# gateway_r0.net
KiCad netlist of a schematic drawn in EAGLE
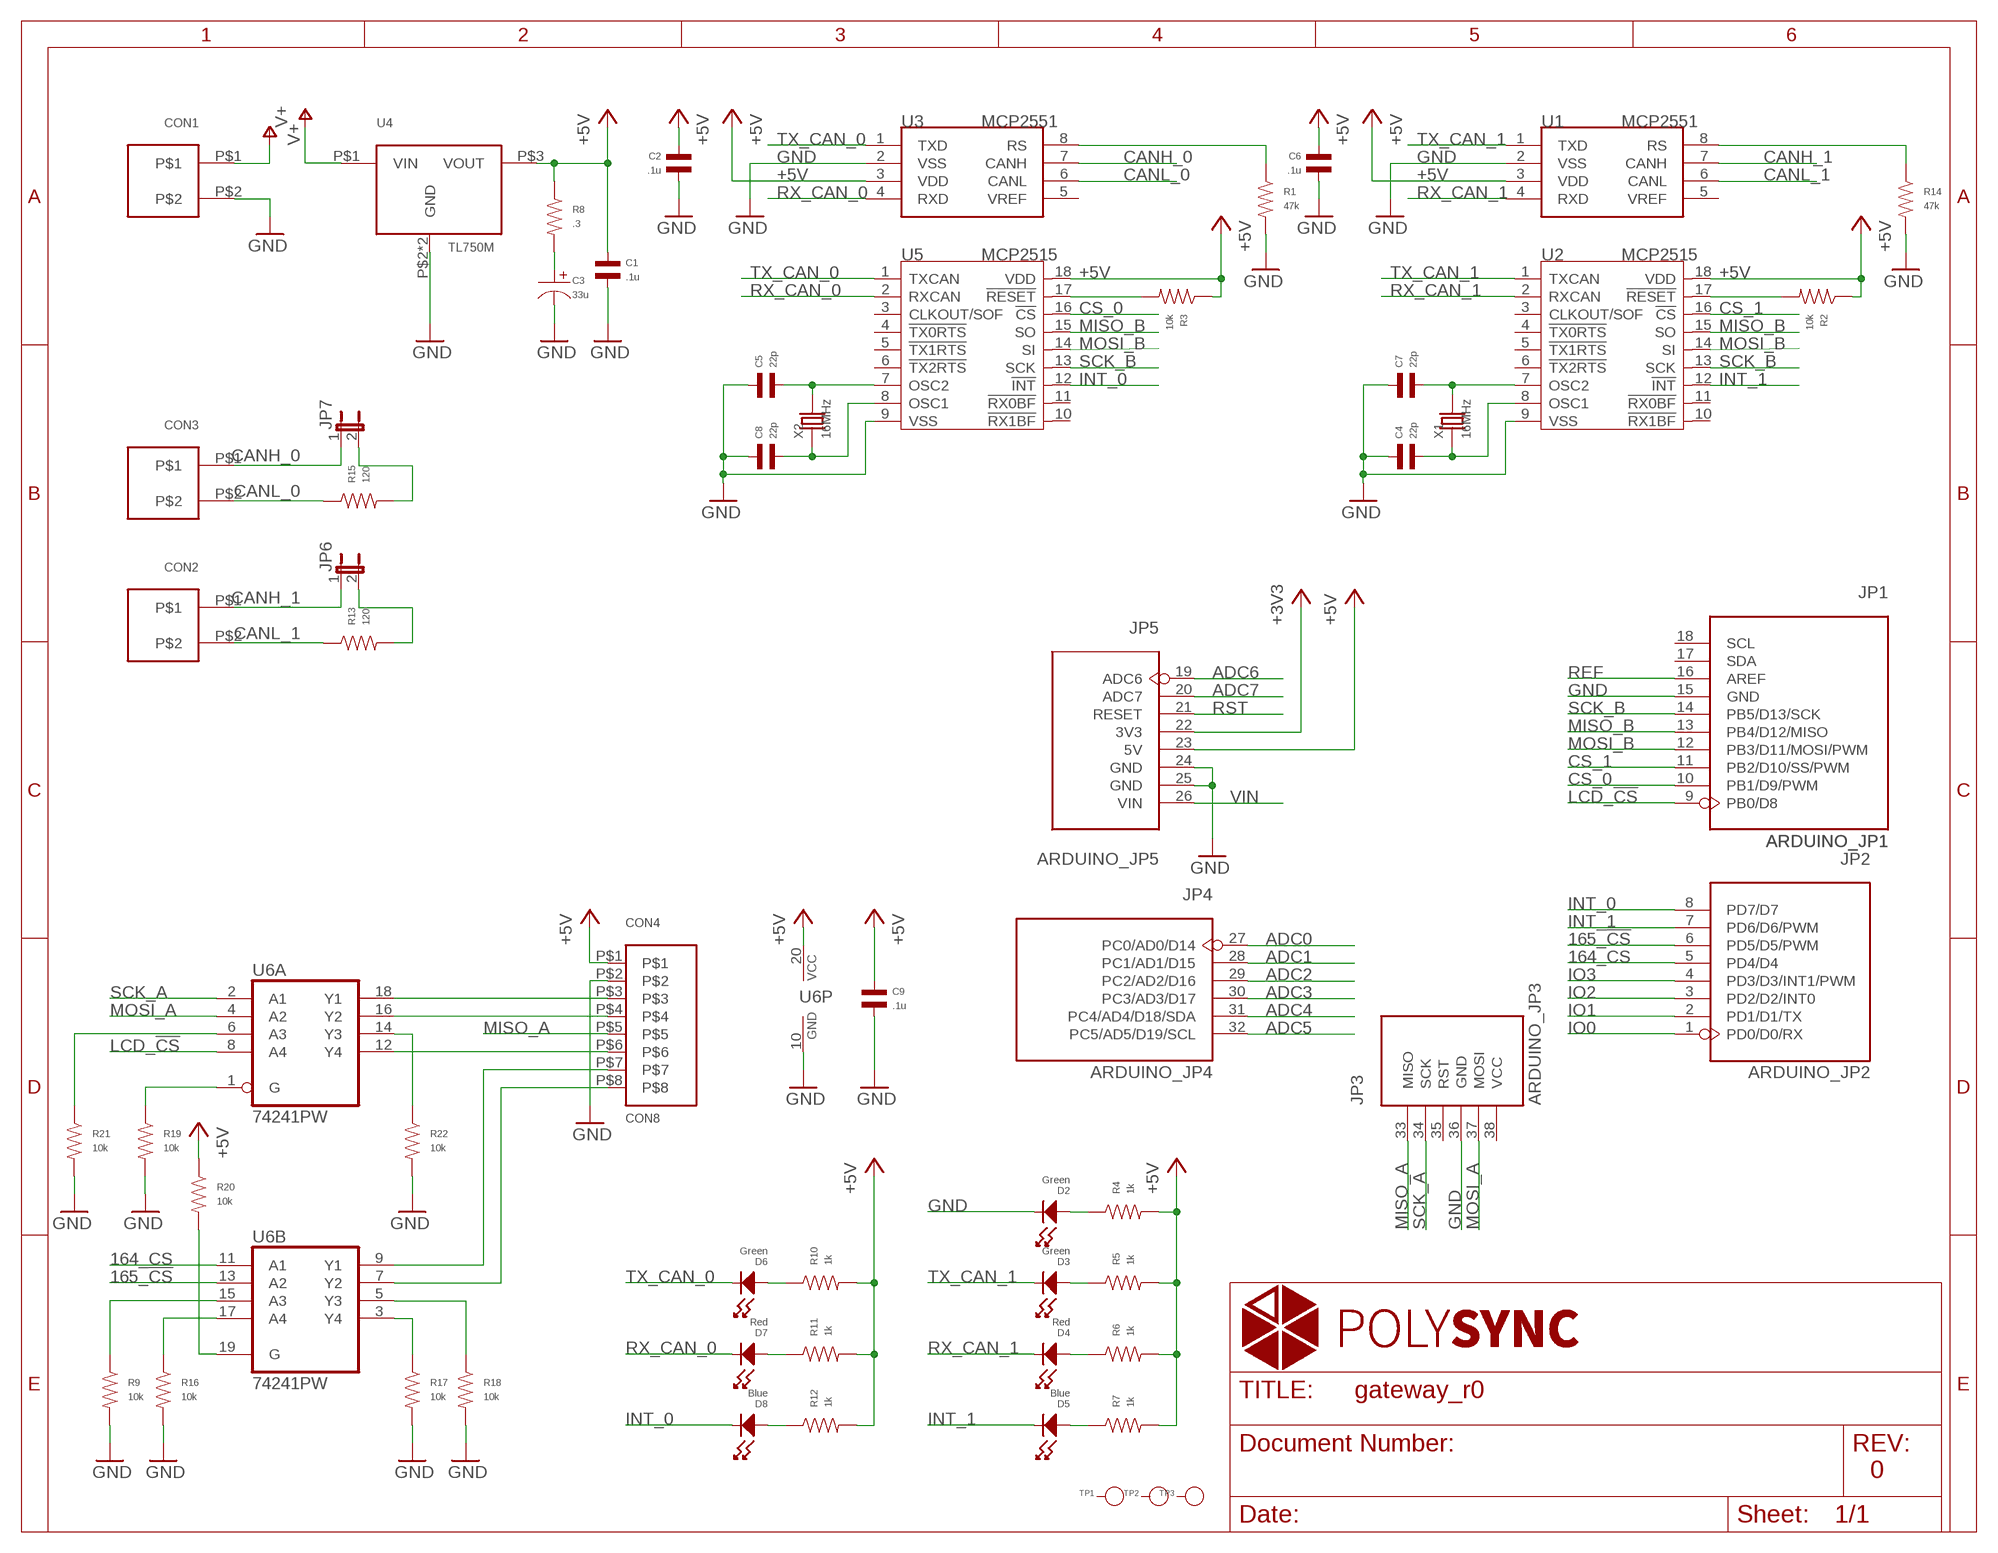
[diagram p0: schematic, sheet 1]

(export (version "E")
  (design (tool "Eeschema 10.0.6"))
  (components
    (comp (ref "C1")
      (value ".1u")
      (footprint "eagle-import:C0402")
      (libsource (lib "eagle-import") (part "CAPACITOR_NP_0402"))
    )
    (comp (ref "C2")
      (value ".1u")
      (footprint "eagle-import:C0402")
      (libsource (lib "eagle-import") (part "CAPACITOR_NP_0402"))
    )
    (comp (ref "C3")
      (value "33u")
      (footprint "eagle-import:CP1206")
      (libsource (lib "eagle-import") (part "CAPACITOR_P"))
    )
    (comp (ref "C4")
      (value "22p")
      (footprint "eagle-import:C0402")
      (libsource (lib "eagle-import") (part "CAPACITOR_NP_0402"))
    )
    (comp (ref "C5")
      (value "22p")
      (footprint "eagle-import:C0402")
      (libsource (lib "eagle-import") (part "CAPACITOR_NP_0402"))
    )
    (comp (ref "C6")
      (value ".1u")
      (footprint "eagle-import:C0402")
      (libsource (lib "eagle-import") (part "CAPACITOR_NP_0402"))
    )
    (comp (ref "C7")
      (value "22p")
      (footprint "eagle-import:C0402")
      (libsource (lib "eagle-import") (part "CAPACITOR_NP_0402"))
    )
    (comp (ref "C8")
      (value "22p")
      (footprint "eagle-import:C0402")
      (libsource (lib "eagle-import") (part "CAPACITOR_NP_0402"))
    )
    (comp (ref "C9")
      (value ".1u")
      (footprint "eagle-import:C0402")
      (libsource (lib "eagle-import") (part "CAPACITOR_NP_0402"))
    )
    (comp (ref "CON1")
      (value "CON23.5MM")
      (footprint "eagle-import:PHOENIX_2_45")
      (libsource (lib "eagle-import") (part "CON23.5MM"))
    )
    (comp (ref "CON2")
      (value "CON23.5MM")
      (footprint "eagle-import:PHOENIX_2_45")
      (libsource (lib "eagle-import") (part "CON23.5MM"))
    )
    (comp (ref "CON3")
      (value "CON23.5MM")
      (footprint "eagle-import:PHOENIX_2_45")
      (libsource (lib "eagle-import") (part "CON23.5MM"))
    )
    (comp (ref "CON4")
      (value "CON8")
      (footprint "eagle-import:PH-8-SM")
      (libsource (lib "eagle-import") (part "CON8"))
    )
    (comp (ref "D2")
      (value "Green")
      (footprint "eagle-import:LED0603")
      (fields (field (name "HOUSEPART") "NO"))
      (libsource (lib "eagle-import") (part "LED_SINGLE-0603"))
    )
    (comp (ref "D3")
      (value "Green")
      (footprint "eagle-import:LED0603")
      (fields (field (name "HOUSEPART") "NO"))
      (libsource (lib "eagle-import") (part "LED_SINGLE-0603"))
    )
    (comp (ref "D4")
      (value "Red")
      (footprint "eagle-import:LED0603")
      (fields (field (name "HOUSEPART") "NO"))
      (libsource (lib "eagle-import") (part "LED_SINGLE-0603"))
    )
    (comp (ref "D5")
      (value "Blue")
      (footprint "eagle-import:LED0603")
      (fields (field (name "HOUSEPART") "NO"))
      (libsource (lib "eagle-import") (part "LED_SINGLE-0603"))
    )
    (comp (ref "D6")
      (value "Green")
      (footprint "eagle-import:LED0603")
      (fields (field (name "HOUSEPART") "NO"))
      (libsource (lib "eagle-import") (part "LED_SINGLE-0603"))
    )
    (comp (ref "D7")
      (value "Red")
      (footprint "eagle-import:LED0603")
      (fields (field (name "HOUSEPART") "NO"))
      (libsource (lib "eagle-import") (part "LED_SINGLE-0603"))
    )
    (comp (ref "D8")
      (value "Blue")
      (footprint "eagle-import:LED0603")
      (fields (field (name "HOUSEPART") "NO"))
      (libsource (lib "eagle-import") (part "LED_SINGLE-0603"))
    )
    (comp (ref "JP1")
      (value "ARDUINO_JP1")
      (footprint "eagle-import:ARDUINO_JP1")
      (libsource (lib "eagle-import") (part "ARDUINO_JP1"))
    )
    (comp (ref "JP2")
      (value "ARDUINO_JP2")
      (footprint "eagle-import:ARDUINO_JP2")
      (libsource (lib "eagle-import") (part "ARDUINO_JP2"))
    )
    (comp (ref "JP3")
      (value "ARDUINO_JP3")
      (footprint "eagle-import:ARDUINO_JP3")
      (libsource (lib "eagle-import") (part "ARDUINO_JP3"))
    )
    (comp (ref "JP4")
      (value "ARDUINO_JP4")
      (footprint "eagle-import:ARDUINO_JP4")
      (libsource (lib "eagle-import") (part "ARDUINO_JP4"))
    )
    (comp (ref "JP5")
      (value "ARDUINO_JP5")
      (footprint "eagle-import:ARDUINO_JP5")
      (libsource (lib "eagle-import") (part "ARDUINO_JP5"))
    )
    (comp (ref "JP6")
      (value "JP1E")
      (footprint "eagle-import:JP1")
      (libsource (lib "eagle-import") (part "JP1E"))
    )
    (comp (ref "JP7")
      (value "JP1E")
      (footprint "eagle-import:JP1")
      (libsource (lib "eagle-import") (part "JP1E"))
    )
    (comp (ref "R1")
      (value "47k")
      (footprint "eagle-import:R0402")
      (libsource (lib "eagle-import") (part "RESISTOR_0402"))
    )
    (comp (ref "R2")
      (value "10k")
      (footprint "eagle-import:R0402")
      (libsource (lib "eagle-import") (part "RESISTOR_0402"))
    )
    (comp (ref "R3")
      (value "10k")
      (footprint "eagle-import:R0402")
      (libsource (lib "eagle-import") (part "RESISTOR_0402"))
    )
    (comp (ref "R4")
      (value "1k")
      (footprint "eagle-import:R0402")
      (libsource (lib "eagle-import") (part "RESISTOR_0402"))
    )
    (comp (ref "R5")
      (value "1k")
      (footprint "eagle-import:R0402")
      (libsource (lib "eagle-import") (part "RESISTOR_0402"))
    )
    (comp (ref "R6")
      (value "1k")
      (footprint "eagle-import:R0402")
      (libsource (lib "eagle-import") (part "RESISTOR_0402"))
    )
    (comp (ref "R7")
      (value "1k")
      (footprint "eagle-import:R0402")
      (libsource (lib "eagle-import") (part "RESISTOR_0402"))
    )
    (comp (ref "R8")
      (value ".3")
      (footprint "eagle-import:R0402")
      (libsource (lib "eagle-import") (part "RESISTOR_0402"))
    )
    (comp (ref "R9")
      (value "10k")
      (footprint "eagle-import:R0402")
      (libsource (lib "eagle-import") (part "RESISTOR_0402"))
    )
    (comp (ref "R10")
      (value "1k")
      (footprint "eagle-import:R0402")
      (libsource (lib "eagle-import") (part "RESISTOR_0402"))
    )
    (comp (ref "R11")
      (value "1k")
      (footprint "eagle-import:R0402")
      (libsource (lib "eagle-import") (part "RESISTOR_0402"))
    )
    (comp (ref "R12")
      (value "1k")
      (footprint "eagle-import:R0402")
      (libsource (lib "eagle-import") (part "RESISTOR_0402"))
    )
    (comp (ref "R13")
      (value "120")
      (footprint "eagle-import:R0402")
      (libsource (lib "eagle-import") (part "RESISTOR_0402"))
    )
    (comp (ref "R14")
      (value "47k")
      (footprint "eagle-import:R0402")
      (libsource (lib "eagle-import") (part "RESISTOR_0402"))
    )
    (comp (ref "R15")
      (value "120")
      (footprint "eagle-import:R0402")
      (libsource (lib "eagle-import") (part "RESISTOR_0402"))
    )
    (comp (ref "R16")
      (value "10k")
      (footprint "eagle-import:R0402")
      (libsource (lib "eagle-import") (part "RESISTOR_0402"))
    )
    (comp (ref "R17")
      (value "10k")
      (footprint "eagle-import:R0402")
      (libsource (lib "eagle-import") (part "RESISTOR_0402"))
    )
    (comp (ref "R18")
      (value "10k")
      (footprint "eagle-import:R0402")
      (libsource (lib "eagle-import") (part "RESISTOR_0402"))
    )
    (comp (ref "R19")
      (value "10k")
      (footprint "eagle-import:R0402")
      (libsource (lib "eagle-import") (part "RESISTOR_0402"))
    )
    (comp (ref "R20")
      (value "10k")
      (footprint "eagle-import:R0402")
      (libsource (lib "eagle-import") (part "RESISTOR_0402"))
    )
    (comp (ref "R21")
      (value "10k")
      (footprint "eagle-import:R0402")
      (libsource (lib "eagle-import") (part "RESISTOR_0402"))
    )
    (comp (ref "R22")
      (value "10k")
      (footprint "eagle-import:R0402")
      (libsource (lib "eagle-import") (part "RESISTOR_0402"))
    )
    (comp (ref "TP1")
      (value "PAD-TEST-POINT'4545'")
      (footprint "eagle-import:TP_4545")
      (fields (field (name "PARTNO") "DNP"))
      (libsource (lib "eagle-import") (part "PAD-TEST-POINT'4545'"))
    )
    (comp (ref "TP2")
      (value "PAD-TEST-POINT'4545'")
      (footprint "eagle-import:TP_4545")
      (fields (field (name "PARTNO") "DNP"))
      (libsource (lib "eagle-import") (part "PAD-TEST-POINT'4545'"))
    )
    (comp (ref "TP3")
      (value "PAD-TEST-POINT'4545'")
      (footprint "eagle-import:TP_4545")
      (fields (field (name "PARTNO") "DNP"))
      (libsource (lib "eagle-import") (part "PAD-TEST-POINT'4545'"))
    )
    (comp (ref "U1")
      (value "MCP2551")
      (footprint "eagle-import:SOIC8-6.0")
      (libsource (lib "eagle-import") (part "MCP2551-SOIC8"))
    )
    (comp (ref "U2")
      (value "MCP2515")
      (footprint "eagle-import:SOIC18")
      (libsource (lib "eagle-import") (part "MCP2515-SOIC18"))
    )
    (comp (ref "U3")
      (value "MCP2551")
      (footprint "eagle-import:SOIC8-6.0")
      (libsource (lib "eagle-import") (part "MCP2551-SOIC8"))
    )
    (comp (ref "U4")
      (value "TL750M")
      (footprint "eagle-import:TO-263")
      (libsource (lib "eagle-import") (part "TL750M"))
    )
    (comp (ref "U5")
      (value "MCP2515")
      (footprint "eagle-import:SOIC18")
      (libsource (lib "eagle-import") (part "MCP2515-SOIC18"))
    )
    (comp (ref "U6")
      (value "74241PW")
      (footprint "eagle-import:PW_R-PDSO-G20")
      (libsource (lib "eagle-import") (part "74241PW"))
    )
    (comp (ref "X1")
      (value "16MHz")
      (footprint "eagle-import:HC49UP")
      (libsource (lib "eagle-import") (part "CRYSTAL-HC49UP"))
    )
    (comp (ref "X2")
      (value "16MHz")
      (footprint "eagle-import:HC49UP")
      (libsource (lib "eagle-import") (part "CRYSTAL-HC49UP"))
    )
  )
  (nets
    (net (code "1") (name "+3V3") (class "Default")
      (node (ref "JP5") (pin "22") (pinfunction "3V3_22") (pintype "bidirectional"))
    )
    (net (code "2") (name "+5V") (class "Default")
      (node (ref "C1") (pin "P$1") (pinfunction "P$1_P$1") (pintype "passive"))
      (node (ref "C2") (pin "P$1") (pinfunction "P$1_P$1") (pintype "passive"))
      (node (ref "C6") (pin "P$1") (pinfunction "P$1_P$1") (pintype "passive"))
      (node (ref "C9") (pin "P$1") (pinfunction "P$1_P$1") (pintype "passive"))
      (node (ref "CON4") (pin "P$1") (pinfunction "P$1_P$1") (pintype "bidirectional"))
      (node (ref "JP5") (pin "23") (pinfunction "5V_23") (pintype "bidirectional"))
      (node (ref "R10") (pin "P$2") (pinfunction "P$2_P$2") (pintype "passive"))
      (node (ref "R11") (pin "P$2") (pinfunction "P$2_P$2") (pintype "passive"))
      (node (ref "R12") (pin "P$2") (pinfunction "P$2_P$2") (pintype "passive"))
      (node (ref "R2") (pin "P$1") (pinfunction "P$1_P$1") (pintype "passive"))
      (node (ref "R20") (pin "P$1") (pinfunction "P$1_P$1") (pintype "passive"))
      (node (ref "R3") (pin "P$1") (pinfunction "P$1_P$1") (pintype "passive"))
      (node (ref "R4") (pin "P$2") (pinfunction "P$2_P$2") (pintype "passive"))
      (node (ref "R5") (pin "P$2") (pinfunction "P$2_P$2") (pintype "passive"))
      (node (ref "R6") (pin "P$2") (pinfunction "P$2_P$2") (pintype "passive"))
      (node (ref "R7") (pin "P$2") (pinfunction "P$2_P$2") (pintype "passive"))
      (node (ref "R8") (pin "P$1") (pinfunction "P$1_P$1") (pintype "passive"))
      (node (ref "U1") (pin "3") (pinfunction "VDD_3") (pintype "bidirectional"))
      (node (ref "U2") (pin "18") (pinfunction "VDD_18") (pintype "power_in"))
      (node (ref "U3") (pin "3") (pinfunction "VDD_3") (pintype "bidirectional"))
      (node (ref "U4") (pin "P$3") (pinfunction "VOUT_P$3") (pintype "bidirectional"))
      (node (ref "U5") (pin "18") (pinfunction "VDD_18") (pintype "power_in"))
      (node (ref "U6") (pin "20") (pinfunction "VCC_20") (pintype "power_in"))
    )
    (net (code "3") (name "/164_CS") (class "Default")
      (node (ref "JP2") (pin "5") (pinfunction "PD4/D4_5") (pintype "bidirectional"))
      (node (ref "U6") (pin "11") (pinfunction "A1_11") (pintype "input"))
    )
    (net (code "4") (name "/165_~{CS}") (class "Default")
      (node (ref "JP2") (pin "6") (pinfunction "PD5/D5/PWM_6") (pintype "bidirectional"))
      (node (ref "U6") (pin "13") (pinfunction "A2_13") (pintype "input"))
    )
    (net (code "5") (name "/ADC0") (class "Default")
      (node (ref "JP4") (pin "27") (pinfunction "PC0/AD0/D14_27") (pintype "bidirectional"))
    )
    (net (code "6") (name "/ADC1") (class "Default")
      (node (ref "JP4") (pin "28") (pinfunction "PC1/AD1/D15_28") (pintype "bidirectional"))
    )
    (net (code "7") (name "/ADC2") (class "Default")
      (node (ref "JP4") (pin "29") (pinfunction "PC2/AD2/D16_29") (pintype "bidirectional"))
    )
    (net (code "8") (name "/ADC3") (class "Default")
      (node (ref "JP4") (pin "30") (pinfunction "PC3/AD3/D17_30") (pintype "bidirectional"))
    )
    (net (code "9") (name "/ADC4") (class "Default")
      (node (ref "JP4") (pin "31") (pinfunction "PC4/AD4/D18/SDA_31") (pintype "bidirectional"))
    )
    (net (code "10") (name "/ADC5") (class "Default")
      (node (ref "JP4") (pin "32") (pinfunction "PC5/AD5/D19/SCL_32") (pintype "bidirectional"))
    )
    (net (code "11") (name "/ADC6") (class "Default")
      (node (ref "JP5") (pin "19") (pinfunction "ADC6_19") (pintype "bidirectional"))
    )
    (net (code "12") (name "/ADC7") (class "Default")
      (node (ref "JP5") (pin "20") (pinfunction "ADC7_20") (pintype "bidirectional"))
    )
    (net (code "13") (name "/CANH_0") (class "Default")
      (node (ref "CON3") (pin "P$1") (pinfunction "P$1_P$1") (pintype "bidirectional"))
      (node (ref "JP7") (pin "1") (pinfunction "1_1") (pintype "passive"))
      (node (ref "U3") (pin "7") (pinfunction "CANH_7") (pintype "bidirectional"))
    )
    (net (code "14") (name "/CANH_1") (class "Default")
      (node (ref "CON2") (pin "P$1") (pinfunction "P$1_P$1") (pintype "bidirectional"))
      (node (ref "JP6") (pin "1") (pinfunction "1_1") (pintype "passive"))
      (node (ref "U1") (pin "7") (pinfunction "CANH_7") (pintype "bidirectional"))
    )
    (net (code "15") (name "/CANL_0") (class "Default")
      (node (ref "CON3") (pin "P$2") (pinfunction "P$2_P$2") (pintype "bidirectional"))
      (node (ref "R15") (pin "P$1") (pinfunction "P$1_P$1") (pintype "passive"))
      (node (ref "U3") (pin "6") (pinfunction "CANL_6") (pintype "bidirectional"))
    )
    (net (code "16") (name "/CANL_1") (class "Default")
      (node (ref "CON2") (pin "P$2") (pinfunction "P$2_P$2") (pintype "bidirectional"))
      (node (ref "R13") (pin "P$1") (pinfunction "P$1_P$1") (pintype "passive"))
      (node (ref "U1") (pin "6") (pinfunction "CANL_6") (pintype "bidirectional"))
    )
    (net (code "17") (name "/CS_0") (class "Default")
      (node (ref "JP1") (pin "10") (pinfunction "PB1/D9/PWM_10") (pintype "bidirectional"))
      (node (ref "U5") (pin "16") (pinfunction "~{CS}_16") (pintype "input"))
    )
    (net (code "18") (name "/CS_1") (class "Default")
      (node (ref "JP1") (pin "11") (pinfunction "PB2/D10/SS/PWM_11") (pintype "bidirectional"))
      (node (ref "U2") (pin "16") (pinfunction "~{CS}_16") (pintype "input"))
    )
    (net (code "19") (name "/INT_0") (class "Default")
      (node (ref "D8") (pin "CATHODE") (pinfunction "CATHODE_CATHODE") (pintype "power_in"))
      (node (ref "JP2") (pin "8") (pinfunction "PD7/D7_8") (pintype "bidirectional"))
      (node (ref "U5") (pin "12") (pinfunction "~{INT}_12") (pintype "output"))
    )
    (net (code "20") (name "/INT_1") (class "Default")
      (node (ref "D5") (pin "CATHODE") (pinfunction "CATHODE_CATHODE") (pintype "power_in"))
      (node (ref "JP2") (pin "7") (pinfunction "PD6/D6/PWM_7") (pintype "bidirectional"))
      (node (ref "U2") (pin "12") (pinfunction "~{INT}_12") (pintype "output"))
    )
    (net (code "21") (name "/IO0") (class "Default")
      (node (ref "JP2") (pin "1") (pinfunction "PD0/D0/RX_1") (pintype "bidirectional"))
    )
    (net (code "22") (name "/IO1") (class "Default")
      (node (ref "JP2") (pin "2") (pinfunction "PD1/D1/TX_2") (pintype "bidirectional"))
    )
    (net (code "23") (name "/IO2") (class "Default")
      (node (ref "JP2") (pin "3") (pinfunction "PD2/D2/INT0_3") (pintype "bidirectional"))
    )
    (net (code "24") (name "/IO3") (class "Default")
      (node (ref "JP2") (pin "4") (pinfunction "PD3/D3/INT1/PWM_4") (pintype "bidirectional"))
    )
    (net (code "25") (name "/LCD_~{CS}") (class "Default")
      (node (ref "JP1") (pin "9") (pinfunction "PB0/D8_9") (pintype "bidirectional"))
      (node (ref "U6") (pin "8") (pinfunction "A4_8") (pintype "input"))
    )
    (net (code "26") (name "/MISO_A") (class "Default")
      (node (ref "CON4") (pin "P$5") (pinfunction "P$5_P$5") (pintype "bidirectional"))
      (node (ref "JP3") (pin "33") (pinfunction "MISO_33") (pintype "bidirectional"))
    )
    (net (code "27") (name "/MISO_B") (class "Default")
      (node (ref "JP1") (pin "13") (pinfunction "PB4/D12/MISO_13") (pintype "bidirectional"))
      (node (ref "U2") (pin "15") (pinfunction "SO_15") (pintype "output"))
      (node (ref "U5") (pin "15") (pinfunction "SO_15") (pintype "output"))
    )
    (net (code "28") (name "/MOSI_A") (class "Default")
      (node (ref "JP3") (pin "37") (pinfunction "MOSI_37") (pintype "bidirectional"))
      (node (ref "U6") (pin "4") (pinfunction "A2_4") (pintype "input"))
    )
    (net (code "29") (name "/MOSI_B") (class "Default")
      (node (ref "JP1") (pin "12") (pinfunction "PB3/D11/MOSI/PWM_12") (pintype "bidirectional"))
      (node (ref "U2") (pin "14") (pinfunction "SI_14") (pintype "input"))
      (node (ref "U5") (pin "14") (pinfunction "SI_14") (pintype "input"))
    )
    (net (code "30") (name "/REF") (class "Default")
      (node (ref "JP1") (pin "16") (pinfunction "AREF_16") (pintype "bidirectional"))
    )
    (net (code "31") (name "/RST") (class "Default")
      (node (ref "JP5") (pin "21") (pinfunction "RESET_21") (pintype "bidirectional"))
    )
    (net (code "32") (name "/RX_CAN_0") (class "Default")
      (node (ref "D7") (pin "CATHODE") (pinfunction "CATHODE_CATHODE") (pintype "power_in"))
      (node (ref "U3") (pin "4") (pinfunction "RXD_4") (pintype "bidirectional"))
      (node (ref "U5") (pin "2") (pinfunction "RXCAN_2") (pintype "input"))
    )
    (net (code "33") (name "/RX_CAN_1") (class "Default")
      (node (ref "D4") (pin "CATHODE") (pinfunction "CATHODE_CATHODE") (pintype "power_in"))
      (node (ref "U1") (pin "4") (pinfunction "RXD_4") (pintype "bidirectional"))
      (node (ref "U2") (pin "2") (pinfunction "RXCAN_2") (pintype "input"))
    )
    (net (code "34") (name "/SCK_A") (class "Default")
      (node (ref "JP3") (pin "34") (pinfunction "SCK_34") (pintype "bidirectional"))
      (node (ref "U6") (pin "2") (pinfunction "A1_2") (pintype "input"))
    )
    (net (code "35") (name "/SCK_B") (class "Default")
      (node (ref "JP1") (pin "14") (pinfunction "PB5/D13/SCK_14") (pintype "bidirectional"))
      (node (ref "U2") (pin "13") (pinfunction "SCK_13") (pintype "input"))
      (node (ref "U5") (pin "13") (pinfunction "SCK_13") (pintype "input"))
    )
    (net (code "36") (name "/TX_CAN_0") (class "Default")
      (node (ref "D6") (pin "CATHODE") (pinfunction "CATHODE_CATHODE") (pintype "power_in"))
      (node (ref "U3") (pin "1") (pinfunction "TXD_1") (pintype "bidirectional"))
      (node (ref "U5") (pin "1") (pinfunction "TXCAN_1") (pintype "output"))
    )
    (net (code "37") (name "/TX_CAN_1") (class "Default")
      (node (ref "D3") (pin "CATHODE") (pinfunction "CATHODE_CATHODE") (pintype "power_in"))
      (node (ref "U1") (pin "1") (pinfunction "TXD_1") (pintype "bidirectional"))
      (node (ref "U2") (pin "1") (pinfunction "TXCAN_1") (pintype "output"))
    )
    (net (code "38") (name "/VIN") (class "Default")
      (node (ref "JP5") (pin "26") (pinfunction "VIN_26") (pintype "bidirectional"))
    )
    (net (code "39") (name "GND") (class "Default")
      (node (ref "C1") (pin "P$2") (pinfunction "P$2_P$2") (pintype "passive"))
      (node (ref "C2") (pin "P$2") (pinfunction "P$2_P$2") (pintype "passive"))
      (node (ref "C3") (pin "P$2") (pinfunction "P$2_P$2") (pintype "passive"))
      (node (ref "C4") (pin "P$1") (pinfunction "P$1_P$1") (pintype "passive"))
      (node (ref "C5") (pin "P$1") (pinfunction "P$1_P$1") (pintype "passive"))
      (node (ref "C6") (pin "P$2") (pinfunction "P$2_P$2") (pintype "passive"))
      (node (ref "C7") (pin "P$1") (pinfunction "P$1_P$1") (pintype "passive"))
      (node (ref "C8") (pin "P$1") (pinfunction "P$1_P$1") (pintype "passive"))
      (node (ref "C9") (pin "P$2") (pinfunction "P$2_P$2") (pintype "passive"))
      (node (ref "CON1") (pin "P$2") (pinfunction "P$2_P$2") (pintype "bidirectional"))
      (node (ref "CON4") (pin "P$2") (pinfunction "P$2_P$2") (pintype "bidirectional"))
      (node (ref "D2") (pin "CATHODE") (pinfunction "CATHODE_CATHODE") (pintype "power_in"))
      (node (ref "JP1") (pin "15") (pinfunction "GND_15") (pintype "bidirectional"))
      (node (ref "JP3") (pin "36") (pinfunction "GND_36") (pintype "bidirectional"))
      (node (ref "JP5") (pin "24") (pinfunction "GND_24") (pintype "bidirectional"))
      (node (ref "JP5") (pin "25") (pinfunction "GND_25") (pintype "bidirectional"))
      (node (ref "R1") (pin "P$2") (pinfunction "P$2_P$2") (pintype "passive"))
      (node (ref "R14") (pin "P$2") (pinfunction "P$2_P$2") (pintype "passive"))
      (node (ref "R16") (pin "P$2") (pinfunction "P$2_P$2") (pintype "passive"))
      (node (ref "R17") (pin "P$2") (pinfunction "P$2_P$2") (pintype "passive"))
      (node (ref "R18") (pin "P$2") (pinfunction "P$2_P$2") (pintype "passive"))
      (node (ref "R19") (pin "P$2") (pinfunction "P$2_P$2") (pintype "passive"))
      (node (ref "R21") (pin "P$2") (pinfunction "P$2_P$2") (pintype "passive"))
      (node (ref "R22") (pin "P$2") (pinfunction "P$2_P$2") (pintype "passive"))
      (node (ref "R9") (pin "P$2") (pinfunction "P$2_P$2") (pintype "passive"))
      (node (ref "U1") (pin "2") (pinfunction "VSS_2") (pintype "bidirectional"))
      (node (ref "U2") (pin "9") (pinfunction "VSS_9") (pintype "power_in"))
      (node (ref "U3") (pin "2") (pinfunction "VSS_2") (pintype "bidirectional"))
      (node (ref "U4") (pin "P$2") (pinfunction "GND_P$2") (pintype "bidirectional"))
      (node (ref "U4") (pin "P$4") (pinfunction "GND_P$4") (pintype "bidirectional"))
      (node (ref "U5") (pin "9") (pinfunction "VSS_9") (pintype "power_in"))
      (node (ref "U6") (pin "10") (pinfunction "GND_10") (pintype "power_in"))
    )
    (net (code "40") (name "Net-(C3-PadP$1)") (class "Default")
      (node (ref "C3") (pin "P$1") (pinfunction "P$1_P$1") (pintype "passive"))
      (node (ref "R8") (pin "P$2") (pinfunction "P$2_P$2") (pintype "passive"))
    )
    (net (code "41") (name "Net-(D2-PadANODE)") (class "Default")
      (node (ref "D2") (pin "ANODE") (pinfunction "ANODE_ANODE") (pintype "power_in"))
      (node (ref "R4") (pin "P$1") (pinfunction "P$1_P$1") (pintype "passive"))
    )
    (net (code "42") (name "Net-(D3-PadANODE)") (class "Default")
      (node (ref "D3") (pin "ANODE") (pinfunction "ANODE_ANODE") (pintype "power_in"))
      (node (ref "R5") (pin "P$1") (pinfunction "P$1_P$1") (pintype "passive"))
    )
    (net (code "43") (name "Net-(D4-PadANODE)") (class "Default")
      (node (ref "D4") (pin "ANODE") (pinfunction "ANODE_ANODE") (pintype "power_in"))
      (node (ref "R6") (pin "P$1") (pinfunction "P$1_P$1") (pintype "passive"))
    )
    (net (code "44") (name "Net-(D5-PadANODE)") (class "Default")
      (node (ref "D5") (pin "ANODE") (pinfunction "ANODE_ANODE") (pintype "power_in"))
      (node (ref "R7") (pin "P$1") (pinfunction "P$1_P$1") (pintype "passive"))
    )
    (net (code "45") (name "Net-(D6-PadANODE)") (class "Default")
      (node (ref "D6") (pin "ANODE") (pinfunction "ANODE_ANODE") (pintype "power_in"))
      (node (ref "R10") (pin "P$1") (pinfunction "P$1_P$1") (pintype "passive"))
    )
    (net (code "46") (name "Net-(D7-PadANODE)") (class "Default")
      (node (ref "D7") (pin "ANODE") (pinfunction "ANODE_ANODE") (pintype "power_in"))
      (node (ref "R11") (pin "P$1") (pinfunction "P$1_P$1") (pintype "passive"))
    )
    (net (code "47") (name "Net-(D8-PadANODE)") (class "Default")
      (node (ref "D8") (pin "ANODE") (pinfunction "ANODE_ANODE") (pintype "power_in"))
      (node (ref "R12") (pin "P$1") (pinfunction "P$1_P$1") (pintype "passive"))
    )
    (net (code "48") (name "Net-(JP6-Pad2)") (class "Default")
      (node (ref "JP6") (pin "2") (pinfunction "2_2") (pintype "passive"))
      (node (ref "R13") (pin "P$2") (pinfunction "P$2_P$2") (pintype "passive"))
    )
    (net (code "49") (name "Net-(JP7-Pad2)") (class "Default")
      (node (ref "JP7") (pin "2") (pinfunction "2_2") (pintype "passive"))
      (node (ref "R15") (pin "P$2") (pinfunction "P$2_P$2") (pintype "passive"))
    )
    (net (code "50") (name "Net-(U1-RS)") (class "Default")
      (node (ref "R14") (pin "P$1") (pinfunction "P$1_P$1") (pintype "passive"))
      (node (ref "U1") (pin "8") (pinfunction "RS_8") (pintype "bidirectional"))
    )
    (net (code "51") (name "Net-(U2-OSC1)") (class "Default")
      (node (ref "C4") (pin "P$2") (pinfunction "P$2_P$2") (pintype "passive"))
      (node (ref "U2") (pin "8") (pinfunction "OSC1_8") (pintype "input"))
      (node (ref "X1") (pin "1") (pinfunction "1_1") (pintype "passive"))
    )
    (net (code "52") (name "Net-(U2-OSC2)") (class "Default")
      (node (ref "C7") (pin "P$2") (pinfunction "P$2_P$2") (pintype "passive"))
      (node (ref "U2") (pin "7") (pinfunction "OSC2_7") (pintype "output"))
      (node (ref "X1") (pin "2") (pinfunction "2_2") (pintype "passive"))
    )
    (net (code "53") (name "Net-(U2-~{RESET})") (class "Default")
      (node (ref "R2") (pin "P$2") (pinfunction "P$2_P$2") (pintype "passive"))
      (node (ref "U2") (pin "17") (pinfunction "~{RESET}_17") (pintype "input"))
    )
    (net (code "54") (name "Net-(U3-RS)") (class "Default")
      (node (ref "R1") (pin "P$1") (pinfunction "P$1_P$1") (pintype "passive"))
      (node (ref "U3") (pin "8") (pinfunction "RS_8") (pintype "bidirectional"))
    )
    (net (code "55") (name "Net-(U5-OSC1)") (class "Default")
      (node (ref "C8") (pin "P$2") (pinfunction "P$2_P$2") (pintype "passive"))
      (node (ref "U5") (pin "8") (pinfunction "OSC1_8") (pintype "input"))
      (node (ref "X2") (pin "1") (pinfunction "1_1") (pintype "passive"))
    )
    (net (code "56") (name "Net-(U5-OSC2)") (class "Default")
      (node (ref "C5") (pin "P$2") (pinfunction "P$2_P$2") (pintype "passive"))
      (node (ref "U5") (pin "7") (pinfunction "OSC2_7") (pintype "output"))
      (node (ref "X2") (pin "2") (pinfunction "2_2") (pintype "passive"))
    )
    (net (code "57") (name "Net-(U5-~{RESET})") (class "Default")
      (node (ref "R3") (pin "P$2") (pinfunction "P$2_P$2") (pintype "passive"))
      (node (ref "U5") (pin "17") (pinfunction "~{RESET}_17") (pintype "input"))
    )
    (net (code "58") (name "Net-(U6A-A3)") (class "Default")
      (node (ref "R21") (pin "P$1") (pinfunction "P$1_P$1") (pintype "passive"))
      (node (ref "U6") (pin "6") (pinfunction "A3_6") (pintype "input"))
    )
    (net (code "59") (name "Net-(U6A-G)") (class "Default")
      (node (ref "R19") (pin "P$1") (pinfunction "P$1_P$1") (pintype "passive"))
      (node (ref "U6") (pin "1") (pinfunction "G_1") (pintype "input"))
    )
    (net (code "60") (name "Net-(U6A-Y1)") (class "Default")
      (node (ref "CON4") (pin "P$3") (pinfunction "P$3_P$3") (pintype "bidirectional"))
      (node (ref "U6") (pin "18") (pinfunction "Y1_18") (pintype "tri_state"))
    )
    (net (code "61") (name "Net-(U6A-Y2)") (class "Default")
      (node (ref "CON4") (pin "P$4") (pinfunction "P$4_P$4") (pintype "bidirectional"))
      (node (ref "U6") (pin "16") (pinfunction "Y2_16") (pintype "tri_state"))
    )
    (net (code "62") (name "Net-(U6A-Y3)") (class "Default")
      (node (ref "R22") (pin "P$1") (pinfunction "P$1_P$1") (pintype "passive"))
      (node (ref "U6") (pin "14") (pinfunction "Y3_14") (pintype "tri_state"))
    )
    (net (code "63") (name "Net-(U6A-Y4)") (class "Default")
      (node (ref "CON4") (pin "P$6") (pinfunction "P$6_P$6") (pintype "bidirectional"))
      (node (ref "U6") (pin "12") (pinfunction "Y4_12") (pintype "tri_state"))
    )
    (net (code "64") (name "Net-(U6B-A3)") (class "Default")
      (node (ref "R9") (pin "P$1") (pinfunction "P$1_P$1") (pintype "passive"))
      (node (ref "U6") (pin "15") (pinfunction "A3_15") (pintype "input"))
    )
    (net (code "65") (name "Net-(U6B-A4)") (class "Default")
      (node (ref "R16") (pin "P$1") (pinfunction "P$1_P$1") (pintype "passive"))
      (node (ref "U6") (pin "17") (pinfunction "A4_17") (pintype "input"))
    )
    (net (code "66") (name "Net-(U6B-G)") (class "Default")
      (node (ref "R20") (pin "P$2") (pinfunction "P$2_P$2") (pintype "passive"))
      (node (ref "U6") (pin "19") (pinfunction "G_19") (pintype "input"))
    )
    (net (code "67") (name "Net-(U6B-Y1)") (class "Default")
      (node (ref "CON4") (pin "P$7") (pinfunction "P$7_P$7") (pintype "bidirectional"))
      (node (ref "U6") (pin "9") (pinfunction "Y1_9") (pintype "tri_state"))
    )
    (net (code "68") (name "Net-(U6B-Y2)") (class "Default")
      (node (ref "CON4") (pin "P$8") (pinfunction "P$8_P$8") (pintype "bidirectional"))
      (node (ref "U6") (pin "7") (pinfunction "Y2_7") (pintype "tri_state"))
    )
    (net (code "69") (name "Net-(U6B-Y3)") (class "Default")
      (node (ref "R18") (pin "P$1") (pinfunction "P$1_P$1") (pintype "passive"))
      (node (ref "U6") (pin "5") (pinfunction "Y3_5") (pintype "tri_state"))
    )
    (net (code "70") (name "Net-(U6B-Y4)") (class "Default")
      (node (ref "R17") (pin "P$1") (pinfunction "P$1_P$1") (pintype "passive"))
      (node (ref "U6") (pin "3") (pinfunction "Y4_3") (pintype "tri_state"))
    )
    (net (code "71") (name "V+") (class "Default")
      (node (ref "CON1") (pin "P$1") (pinfunction "P$1_P$1") (pintype "bidirectional"))
      (node (ref "U4") (pin "P$1") (pinfunction "VIN_P$1") (pintype "bidirectional"))
    )
    (net (code "72") (name "unconnected-(JP1-SCL-Pad18)") (class "Default")
      (node (ref "JP1") (pin "18") (pinfunction "SCL_18") (pintype "bidirectional"))
    )
    (net (code "73") (name "unconnected-(JP1-SDA-Pad17)") (class "Default")
      (node (ref "JP1") (pin "17") (pinfunction "SDA_17") (pintype "bidirectional"))
    )
    (net (code "74") (name "unconnected-(JP3-RST-Pad35)") (class "Default")
      (node (ref "JP3") (pin "35") (pinfunction "RST_35") (pintype "bidirectional"))
    )
    (net (code "75") (name "unconnected-(JP3-VCC-Pad38)") (class "Default")
      (node (ref "JP3") (pin "38") (pinfunction "VCC_38") (pintype "bidirectional"))
    )
    (net (code "76") (name "unconnected-(TP1-PadT)") (class "Default")
      (node (ref "TP1") (pin "T") (pinfunction "T_T") (pintype "bidirectional"))
    )
    (net (code "77") (name "unconnected-(TP2-PadT)") (class "Default")
      (node (ref "TP2") (pin "T") (pinfunction "T_T") (pintype "bidirectional"))
    )
    (net (code "78") (name "unconnected-(TP3-PadT)") (class "Default")
      (node (ref "TP3") (pin "T") (pinfunction "T_T") (pintype "bidirectional"))
    )
    (net (code "79") (name "unconnected-(U1-VREF-Pad5)") (class "Default")
      (node (ref "U1") (pin "5") (pinfunction "VREF_5") (pintype "bidirectional"))
    )
    (net (code "80") (name "unconnected-(U2-CLKOUT{slash}SOF-Pad3)") (class "Default")
      (node (ref "U2") (pin "3") (pinfunction "CLKOUT/SOF_3") (pintype "output"))
    )
    (net (code "81") (name "unconnected-(U2-~{RX0BF}-Pad11)") (class "Default")
      (node (ref "U2") (pin "11") (pinfunction "~{RX0BF}_11") (pintype "output"))
    )
    (net (code "82") (name "unconnected-(U2-~{RX1BF}-Pad10)") (class "Default")
      (node (ref "U2") (pin "10") (pinfunction "~{RX1BF}_10") (pintype "output"))
    )
    (net (code "83") (name "unconnected-(U2-~{TX0RTS}-Pad4)") (class "Default")
      (node (ref "U2") (pin "4") (pinfunction "~{TX0RTS}_4") (pintype "input"))
    )
    (net (code "84") (name "unconnected-(U2-~{TX1RTS}-Pad5)") (class "Default")
      (node (ref "U2") (pin "5") (pinfunction "~{TX1RTS}_5") (pintype "input"))
    )
    (net (code "85") (name "unconnected-(U2-~{TX2RTS}-Pad6)") (class "Default")
      (node (ref "U2") (pin "6") (pinfunction "~{TX2RTS}_6") (pintype "input"))
    )
    (net (code "86") (name "unconnected-(U3-VREF-Pad5)") (class "Default")
      (node (ref "U3") (pin "5") (pinfunction "VREF_5") (pintype "bidirectional"))
    )
    (net (code "87") (name "unconnected-(U5-CLKOUT{slash}SOF-Pad3)") (class "Default")
      (node (ref "U5") (pin "3") (pinfunction "CLKOUT/SOF_3") (pintype "output"))
    )
    (net (code "88") (name "unconnected-(U5-~{RX0BF}-Pad11)") (class "Default")
      (node (ref "U5") (pin "11") (pinfunction "~{RX0BF}_11") (pintype "output"))
    )
    (net (code "89") (name "unconnected-(U5-~{RX1BF}-Pad10)") (class "Default")
      (node (ref "U5") (pin "10") (pinfunction "~{RX1BF}_10") (pintype "output"))
    )
    (net (code "90") (name "unconnected-(U5-~{TX0RTS}-Pad4)") (class "Default")
      (node (ref "U5") (pin "4") (pinfunction "~{TX0RTS}_4") (pintype "input"))
    )
    (net (code "91") (name "unconnected-(U5-~{TX1RTS}-Pad5)") (class "Default")
      (node (ref "U5") (pin "5") (pinfunction "~{TX1RTS}_5") (pintype "input"))
    )
    (net (code "92") (name "unconnected-(U5-~{TX2RTS}-Pad6)") (class "Default")
      (node (ref "U5") (pin "6") (pinfunction "~{TX2RTS}_6") (pintype "input"))
    )
  )
)
